# dekodery.net
KiCad netlist of a schematic drawn in EAGLE
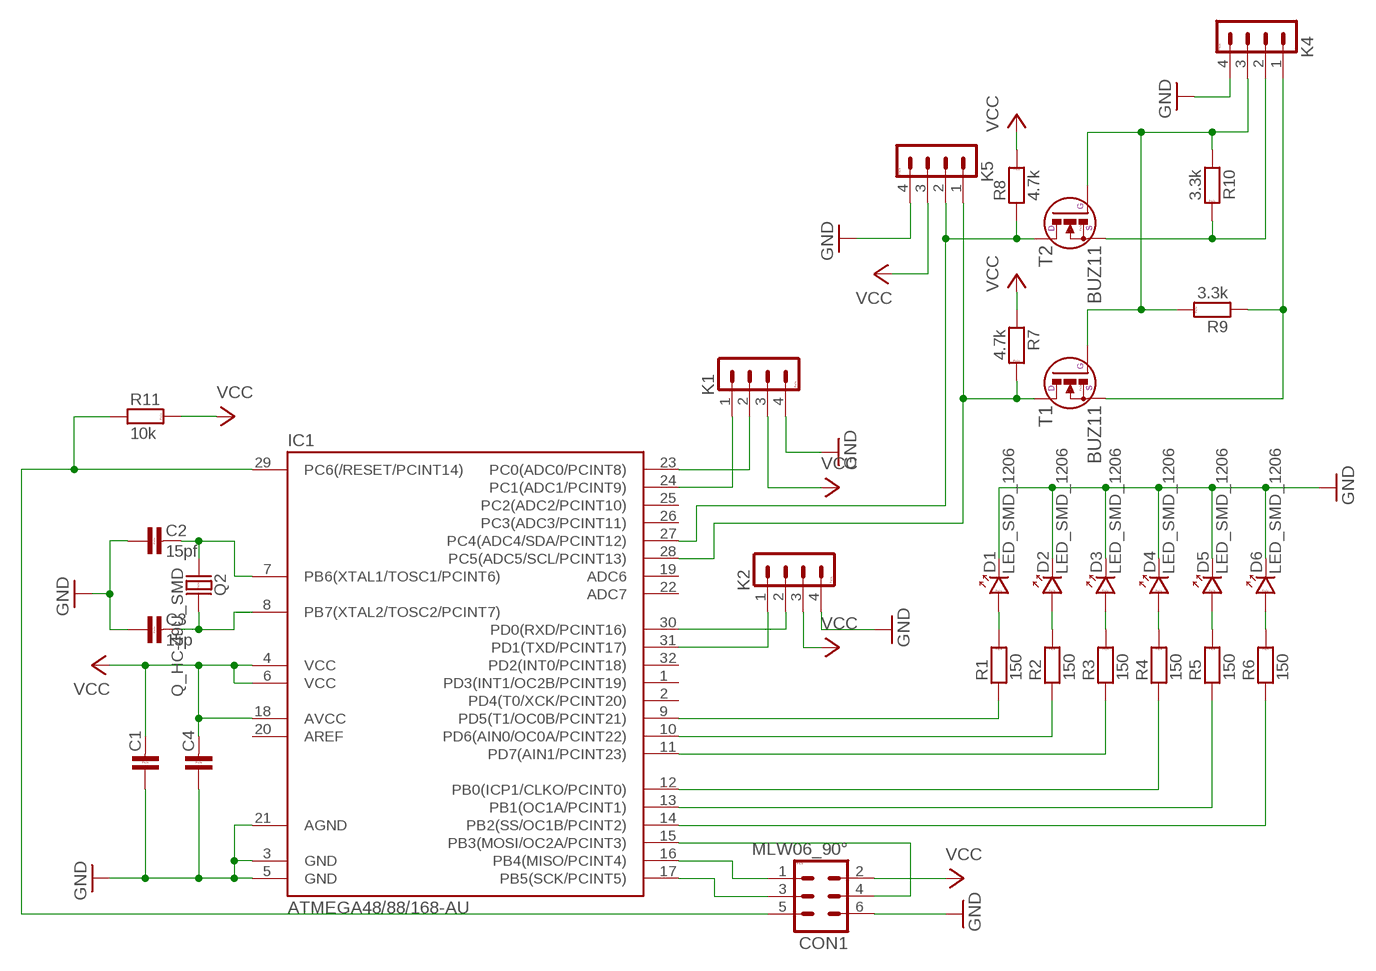
[diagram p0: schematic, sheet 1]

(export (version "E")
  (design (tool "Eeschema 10.0.6"))
  (components
    (comp (ref "C1")
      (value "C-KERAMIK_SMD_1206")
      (footprint "eagle-import:1206")
      (libsource (lib "eagle-import") (part "C-KERAMIK_SMD_1206"))
    )
    (comp (ref "C2")
      (value "15pf")
      (footprint "eagle-import:1206")
      (libsource (lib "eagle-import") (part "C-KERAMIK_SMD_1206"))
    )
    (comp (ref "C3")
      (value "15p")
      (footprint "eagle-import:1206")
      (libsource (lib "eagle-import") (part "C-KERAMIK_SMD_1206"))
    )
    (comp (ref "C4")
      (value "C-KERAMIK_SMD_1206")
      (footprint "eagle-import:1206")
      (libsource (lib "eagle-import") (part "C-KERAMIK_SMD_1206"))
    )
    (comp (ref "CON1")
      (value "MLW06_90°")
      (footprint "eagle-import:MLW06A")
      (libsource (lib "eagle-import") (part "MLW06_90°"))
    )
    (comp (ref "D1")
      (value "LED_SMD_1206")
      (footprint "eagle-import:P1206")
      (libsource (lib "eagle-import") (part "LED_SMD_1206"))
    )
    (comp (ref "D2")
      (value "LED_SMD_1206")
      (footprint "eagle-import:P1206")
      (libsource (lib "eagle-import") (part "LED_SMD_1206"))
    )
    (comp (ref "D3")
      (value "LED_SMD_1206")
      (footprint "eagle-import:P1206")
      (libsource (lib "eagle-import") (part "LED_SMD_1206"))
    )
    (comp (ref "D4")
      (value "LED_SMD_1206")
      (footprint "eagle-import:P1206")
      (libsource (lib "eagle-import") (part "LED_SMD_1206"))
    )
    (comp (ref "D5")
      (value "LED_SMD_1206")
      (footprint "eagle-import:P1206")
      (libsource (lib "eagle-import") (part "LED_SMD_1206"))
    )
    (comp (ref "D6")
      (value "LED_SMD_1206")
      (footprint "eagle-import:P1206")
      (libsource (lib "eagle-import") (part "LED_SMD_1206"))
    )
    (comp (ref "IC1")
      (value "ATMEGA48/88/168-AU")
      (footprint "eagle-import:TQFP32-08")
      (libsource (lib "eagle-import") (part "ATMEGA48/88/168-AU"))
    )
    (comp (ref "K1")
      (value "PSH02-04W")
      (footprint "eagle-import:PSH02-04W")
      (libsource (lib "eagle-import") (part "PSH02-04W"))
    )
    (comp (ref "K2")
      (value "PSH02-04W")
      (footprint "eagle-import:PSH02-04W")
      (libsource (lib "eagle-import") (part "PSH02-04W"))
    )
    (comp (ref "K4")
      (value "PSH02-04W")
      (footprint "eagle-import:PSH02-04W")
      (libsource (lib "eagle-import") (part "PSH02-04W"))
    )
    (comp (ref "K5")
      (value "PSH02-04W")
      (footprint "eagle-import:PSH02-04W")
      (libsource (lib "eagle-import") (part "PSH02-04W"))
    )
    (comp (ref "Q2")
      (value "Q_HC-49U_SMD")
      (footprint "eagle-import:HC-49US")
      (libsource (lib "eagle-import") (part "Q_HC-49U_SMD"))
    )
    (comp (ref "R1")
      (value "150")
      (footprint "eagle-import:1206")
      (libsource (lib "eagle-import") (part "R_SMD_1206"))
    )
    (comp (ref "R2")
      (value "150")
      (footprint "eagle-import:1206")
      (libsource (lib "eagle-import") (part "R_SMD_1206"))
    )
    (comp (ref "R3")
      (value "150")
      (footprint "eagle-import:1206")
      (libsource (lib "eagle-import") (part "R_SMD_1206"))
    )
    (comp (ref "R4")
      (value "150")
      (footprint "eagle-import:1206")
      (libsource (lib "eagle-import") (part "R_SMD_1206"))
    )
    (comp (ref "R5")
      (value "150")
      (footprint "eagle-import:1206")
      (libsource (lib "eagle-import") (part "R_SMD_1206"))
    )
    (comp (ref "R6")
      (value "150")
      (footprint "eagle-import:1206")
      (libsource (lib "eagle-import") (part "R_SMD_1206"))
    )
    (comp (ref "R7")
      (value "4.7k")
      (footprint "eagle-import:1206")
      (libsource (lib "eagle-import") (part "R_SMD_1206"))
    )
    (comp (ref "R8")
      (value "4.7k")
      (footprint "eagle-import:1206")
      (libsource (lib "eagle-import") (part "R_SMD_1206"))
    )
    (comp (ref "R9")
      (value "3.3k")
      (footprint "eagle-import:1206")
      (libsource (lib "eagle-import") (part "R_SMD_1206"))
    )
    (comp (ref "R10")
      (value "3.3k")
      (footprint "eagle-import:1206")
      (libsource (lib "eagle-import") (part "R_SMD_1206"))
    )
    (comp (ref "R11")
      (value "10k")
      (footprint "eagle-import:1206")
      (libsource (lib "eagle-import") (part "R_SMD_1206"))
    )
    (comp (ref "T1")
      (value "BUZ11")
      (footprint "eagle-import:SOT23")
      (libsource (lib "eagle-import") (part "BUZ11"))
    )
    (comp (ref "T2")
      (value "BUZ11")
      (footprint "eagle-import:SOT23")
      (libsource (lib "eagle-import") (part "BUZ11"))
    )
  )
  (nets
    (net (code "1") (name "GND") (class "Default")
      (node (ref "C1") (pin "1") (pinfunction "1_1") (pintype "passive"))
      (node (ref "C2") (pin "1") (pinfunction "1_1") (pintype "passive"))
      (node (ref "C3") (pin "1") (pinfunction "1_1") (pintype "passive"))
      (node (ref "C4") (pin "1") (pinfunction "1_1") (pintype "passive"))
      (node (ref "CON1") (pin "6") (pinfunction "6_6") (pintype "passive"))
      (node (ref "D1") (pin "K") (pinfunction "K_K") (pintype "passive"))
      (node (ref "D2") (pin "K") (pinfunction "K_K") (pintype "passive"))
      (node (ref "D3") (pin "K") (pinfunction "K_K") (pintype "passive"))
      (node (ref "D4") (pin "K") (pinfunction "K_K") (pintype "passive"))
      (node (ref "D5") (pin "K") (pinfunction "K_K") (pintype "passive"))
      (node (ref "D6") (pin "K") (pinfunction "K_K") (pintype "passive"))
      (node (ref "IC1") (pin "21") (pinfunction "AGND_21") (pintype "power_in"))
      (node (ref "IC1") (pin "3") (pinfunction "GND_3") (pintype "power_in"))
      (node (ref "IC1") (pin "5") (pinfunction "GND_5") (pintype "power_in"))
      (node (ref "K1") (pin "4") (pinfunction "4_4") (pintype "passive"))
      (node (ref "K2") (pin "4") (pinfunction "4_4") (pintype "passive"))
      (node (ref "K4") (pin "4") (pinfunction "4_4") (pintype "passive"))
      (node (ref "K5") (pin "4") (pinfunction "4_4") (pintype "passive"))
    )
    (net (code "2") (name "Net-(D1-PadA)") (class "Default")
      (node (ref "D1") (pin "A") (pinfunction "A_A") (pintype "passive"))
      (node (ref "R1") (pin "2") (pinfunction "2_2") (pintype "passive"))
    )
    (net (code "3") (name "Net-(D2-PadA)") (class "Default")
      (node (ref "D2") (pin "A") (pinfunction "A_A") (pintype "passive"))
      (node (ref "R2") (pin "2") (pinfunction "2_2") (pintype "passive"))
    )
    (net (code "4") (name "Net-(D3-PadA)") (class "Default")
      (node (ref "D3") (pin "A") (pinfunction "A_A") (pintype "passive"))
      (node (ref "R3") (pin "2") (pinfunction "2_2") (pintype "passive"))
    )
    (net (code "5") (name "Net-(D4-PadA)") (class "Default")
      (node (ref "D4") (pin "A") (pinfunction "A_A") (pintype "passive"))
      (node (ref "R4") (pin "2") (pinfunction "2_2") (pintype "passive"))
    )
    (net (code "6") (name "Net-(D5-PadA)") (class "Default")
      (node (ref "D5") (pin "A") (pinfunction "A_A") (pintype "passive"))
      (node (ref "R5") (pin "2") (pinfunction "2_2") (pintype "passive"))
    )
    (net (code "7") (name "Net-(D6-PadA)") (class "Default")
      (node (ref "D6") (pin "A") (pinfunction "A_A") (pintype "passive"))
      (node (ref "R6") (pin "2") (pinfunction "2_2") (pintype "passive"))
    )
    (net (code "8") (name "Net-(IC1-PB0(ICP1{slash}CLKO{slash}PCINT0))") (class "Default")
      (node (ref "IC1") (pin "12") (pinfunction "PB0(ICP1/CLKO/PCINT0)_12") (pintype "bidirectional"))
      (node (ref "R4") (pin "1") (pinfunction "1_1") (pintype "passive"))
    )
    (net (code "9") (name "Net-(IC1-PB1(OC1A{slash}PCINT1))") (class "Default")
      (node (ref "IC1") (pin "13") (pinfunction "PB1(OC1A/PCINT1)_13") (pintype "bidirectional"))
      (node (ref "R5") (pin "1") (pinfunction "1_1") (pintype "passive"))
    )
    (net (code "10") (name "Net-(IC1-PB2(SS{slash}OC1B{slash}PCINT2))") (class "Default")
      (node (ref "IC1") (pin "14") (pinfunction "PB2(SS/OC1B/PCINT2)_14") (pintype "bidirectional"))
      (node (ref "R6") (pin "1") (pinfunction "1_1") (pintype "passive"))
    )
    (net (code "11") (name "Net-(IC1-PB3(MOSI{slash}OC2A{slash}PCINT3))") (class "Default")
      (node (ref "CON1") (pin "4") (pinfunction "4_4") (pintype "passive"))
      (node (ref "IC1") (pin "15") (pinfunction "PB3(MOSI/OC2A/PCINT3)_15") (pintype "bidirectional"))
    )
    (net (code "12") (name "Net-(IC1-PB4(MISO{slash}PCINT4))") (class "Default")
      (node (ref "CON1") (pin "1") (pinfunction "1_1") (pintype "passive"))
      (node (ref "IC1") (pin "16") (pinfunction "PB4(MISO/PCINT4)_16") (pintype "bidirectional"))
    )
    (net (code "13") (name "Net-(IC1-PB5(SCK{slash}PCINT5))") (class "Default")
      (node (ref "CON1") (pin "3") (pinfunction "3_3") (pintype "passive"))
      (node (ref "IC1") (pin "17") (pinfunction "PB5(SCK/PCINT5)_17") (pintype "bidirectional"))
    )
    (net (code "14") (name "Net-(IC1-PB6(XTAL1{slash}TOSC1{slash}PCINT6))") (class "Default")
      (node (ref "C2") (pin "2") (pinfunction "2_2") (pintype "passive"))
      (node (ref "IC1") (pin "7") (pinfunction "PB6(XTAL1/TOSC1/PCINT6)_7") (pintype "bidirectional"))
      (node (ref "Q2") (pin "1") (pinfunction "1_1") (pintype "passive"))
    )
    (net (code "15") (name "Net-(IC1-PB7(XTAL2{slash}TOSC2{slash}PCINT7))") (class "Default")
      (node (ref "C3") (pin "2") (pinfunction "2_2") (pintype "passive"))
      (node (ref "IC1") (pin "8") (pinfunction "PB7(XTAL2/TOSC2/PCINT7)_8") (pintype "bidirectional"))
      (node (ref "Q2") (pin "2") (pinfunction "2_2") (pintype "passive"))
    )
    (net (code "16") (name "Net-(IC1-PC0(ADC0{slash}PCINT8))") (class "Default")
      (node (ref "IC1") (pin "23") (pinfunction "PC0(ADC0/PCINT8)_23") (pintype "bidirectional"))
      (node (ref "K1") (pin "2") (pinfunction "2_2") (pintype "passive"))
    )
    (net (code "17") (name "Net-(IC1-PC1(ADC1{slash}PCINT9))") (class "Default")
      (node (ref "IC1") (pin "24") (pinfunction "PC1(ADC1/PCINT9)_24") (pintype "bidirectional"))
      (node (ref "K1") (pin "1") (pinfunction "1_1") (pintype "passive"))
    )
    (net (code "18") (name "Net-(IC1-PC4(ADC4{slash}SDA{slash}PCINT12))") (class "Default")
      (node (ref "IC1") (pin "27") (pinfunction "PC4(ADC4/SDA/PCINT12)_27") (pintype "bidirectional"))
      (node (ref "K5") (pin "2") (pinfunction "2_2") (pintype "passive"))
      (node (ref "R8") (pin "1") (pinfunction "1_1") (pintype "passive"))
      (node (ref "T2") (pin "3") (pinfunction "D_3") (pintype "passive"))
    )
    (net (code "19") (name "Net-(IC1-PC5(ADC5{slash}SCL{slash}PCINT13))") (class "Default")
      (node (ref "IC1") (pin "28") (pinfunction "PC5(ADC5/SCL/PCINT13)_28") (pintype "bidirectional"))
      (node (ref "K5") (pin "1") (pinfunction "1_1") (pintype "passive"))
      (node (ref "R7") (pin "2") (pinfunction "2_2") (pintype "passive"))
      (node (ref "T1") (pin "3") (pinfunction "D_3") (pintype "passive"))
    )
    (net (code "20") (name "Net-(IC1-PC6({slash}RESET{slash}PCINT14))") (class "Default")
      (node (ref "CON1") (pin "5") (pinfunction "5_5") (pintype "passive"))
      (node (ref "IC1") (pin "29") (pinfunction "PC6(/RESET/PCINT14)_29") (pintype "bidirectional"))
      (node (ref "R11") (pin "1") (pinfunction "1_1") (pintype "passive"))
    )
    (net (code "21") (name "Net-(IC1-PD0(RXD{slash}PCINT16))") (class "Default")
      (node (ref "IC1") (pin "30") (pinfunction "PD0(RXD/PCINT16)_30") (pintype "bidirectional"))
      (node (ref "K2") (pin "2") (pinfunction "2_2") (pintype "passive"))
    )
    (net (code "22") (name "Net-(IC1-PD1(TXD{slash}PCINT17))") (class "Default")
      (node (ref "IC1") (pin "31") (pinfunction "PD1(TXD/PCINT17)_31") (pintype "bidirectional"))
      (node (ref "K2") (pin "1") (pinfunction "1_1") (pintype "passive"))
    )
    (net (code "23") (name "Net-(IC1-PD5(T1{slash}OC0B{slash}PCINT21))") (class "Default")
      (node (ref "IC1") (pin "9") (pinfunction "PD5(T1/OC0B/PCINT21)_9") (pintype "bidirectional"))
      (node (ref "R1") (pin "1") (pinfunction "1_1") (pintype "passive"))
    )
    (net (code "24") (name "Net-(IC1-PD6(AIN0{slash}OC0A{slash}PCINT22))") (class "Default")
      (node (ref "IC1") (pin "10") (pinfunction "PD6(AIN0/OC0A/PCINT22)_10") (pintype "bidirectional"))
      (node (ref "R2") (pin "1") (pinfunction "1_1") (pintype "passive"))
    )
    (net (code "25") (name "Net-(IC1-PD7(AIN1{slash}PCINT23))") (class "Default")
      (node (ref "IC1") (pin "11") (pinfunction "PD7(AIN1/PCINT23)_11") (pintype "bidirectional"))
      (node (ref "R3") (pin "1") (pinfunction "1_1") (pintype "passive"))
    )
    (net (code "26") (name "Net-(T1-G)") (class "Default")
      (node (ref "K4") (pin "3") (pinfunction "3_3") (pintype "passive"))
      (node (ref "R10") (pin "1") (pinfunction "1_1") (pintype "passive"))
      (node (ref "R9") (pin "2") (pinfunction "2_2") (pintype "passive"))
      (node (ref "T1") (pin "1") (pinfunction "G_1") (pintype "passive"))
      (node (ref "T2") (pin "1") (pinfunction "G_1") (pintype "passive"))
    )
    (net (code "27") (name "Net-(T1-S)") (class "Default")
      (node (ref "K4") (pin "1") (pinfunction "1_1") (pintype "passive"))
      (node (ref "R9") (pin "1") (pinfunction "1_1") (pintype "passive"))
      (node (ref "T1") (pin "2") (pinfunction "S_2") (pintype "passive"))
    )
    (net (code "28") (name "Net-(T2-S)") (class "Default")
      (node (ref "K4") (pin "2") (pinfunction "2_2") (pintype "passive"))
      (node (ref "R10") (pin "2") (pinfunction "2_2") (pintype "passive"))
      (node (ref "T2") (pin "2") (pinfunction "S_2") (pintype "passive"))
    )
    (net (code "29") (name "VCC") (class "Default")
      (node (ref "C1") (pin "2") (pinfunction "2_2") (pintype "passive"))
      (node (ref "C4") (pin "2") (pinfunction "2_2") (pintype "passive"))
      (node (ref "CON1") (pin "2") (pinfunction "2_2") (pintype "passive"))
      (node (ref "IC1") (pin "18") (pinfunction "AVCC_18") (pintype "passive"))
      (node (ref "IC1") (pin "4") (pinfunction "VCC_4") (pintype "power_in"))
      (node (ref "IC1") (pin "6") (pinfunction "VCC_6") (pintype "power_in"))
      (node (ref "K1") (pin "3") (pinfunction "3_3") (pintype "passive"))
      (node (ref "K2") (pin "3") (pinfunction "3_3") (pintype "passive"))
      (node (ref "K5") (pin "3") (pinfunction "3_3") (pintype "passive"))
      (node (ref "R11") (pin "2") (pinfunction "2_2") (pintype "passive"))
      (node (ref "R7") (pin "1") (pinfunction "1_1") (pintype "passive"))
      (node (ref "R8") (pin "2") (pinfunction "2_2") (pintype "passive"))
    )
    (net (code "30") (name "unconnected-(IC1-ADC6-Pad19)") (class "Default")
      (node (ref "IC1") (pin "19") (pinfunction "ADC6_19") (pintype "passive"))
    )
    (net (code "31") (name "unconnected-(IC1-ADC7-Pad22)") (class "Default")
      (node (ref "IC1") (pin "22") (pinfunction "ADC7_22") (pintype "passive"))
    )
    (net (code "32") (name "unconnected-(IC1-AREF-Pad20)") (class "Default")
      (node (ref "IC1") (pin "20") (pinfunction "AREF_20") (pintype "passive"))
    )
    (net (code "33") (name "unconnected-(IC1-PC2(ADC2{slash}PCINT10)-Pad25)") (class "Default")
      (node (ref "IC1") (pin "25") (pinfunction "PC2(ADC2/PCINT10)_25") (pintype "bidirectional"))
    )
    (net (code "34") (name "unconnected-(IC1-PC3(ADC3{slash}PCINT11)-Pad26)") (class "Default")
      (node (ref "IC1") (pin "26") (pinfunction "PC3(ADC3/PCINT11)_26") (pintype "bidirectional"))
    )
    (net (code "35") (name "unconnected-(IC1-PD2(INT0{slash}PCINT18)-Pad32)") (class "Default")
      (node (ref "IC1") (pin "32") (pinfunction "PD2(INT0/PCINT18)_32") (pintype "bidirectional"))
    )
    (net (code "36") (name "unconnected-(IC1-PD3(INT1{slash}OC2B{slash}PCINT19)-Pad1)") (class "Default")
      (node (ref "IC1") (pin "1") (pinfunction "PD3(INT1/OC2B/PCINT19)_1") (pintype "bidirectional"))
    )
    (net (code "37") (name "unconnected-(IC1-PD4(T0{slash}XCK{slash}PCINT20)-Pad2)") (class "Default")
      (node (ref "IC1") (pin "2") (pinfunction "PD4(T0/XCK/PCINT20)_2") (pintype "bidirectional"))
    )
  )
)
